# 2_Periph.net
KiCad netlist of a schematic drawn in Altium Designer
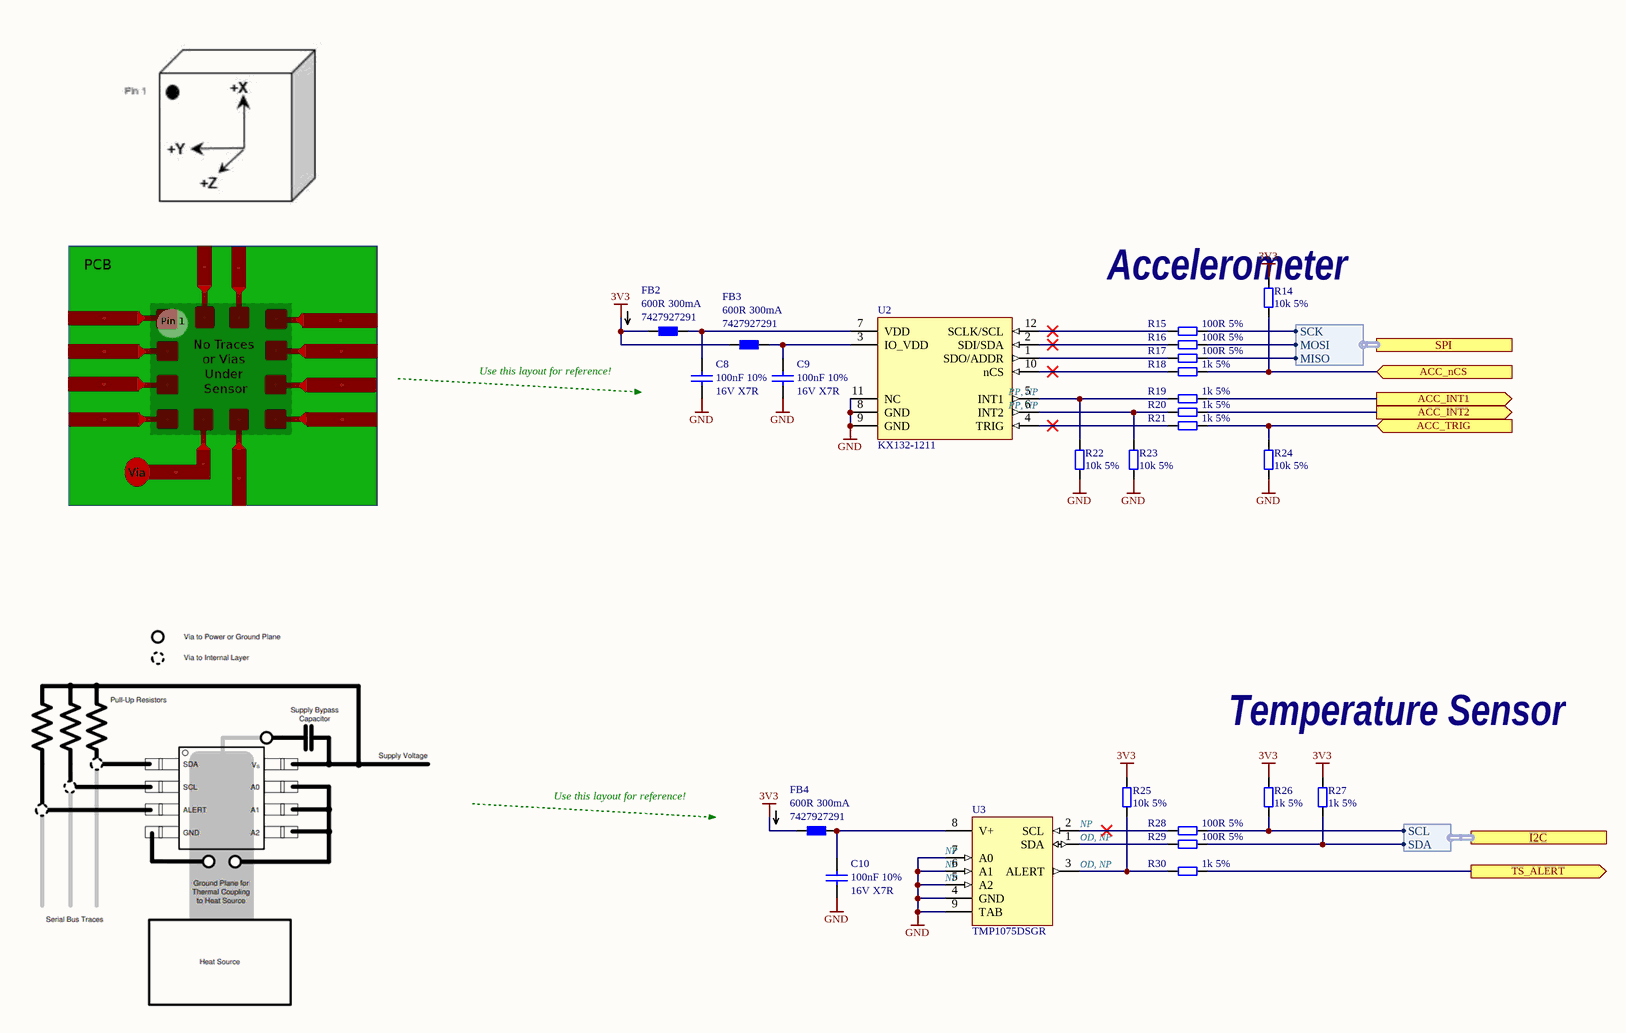
[diagram p0: 2_Periph.SchDoc]

(export (version "E")
  (design (tool "Eeschema 10.0.6"))
  (components
    (comp (ref "C8")
      (value "CC0402KRX7R7BB104")
      (footprint "CAP_0402_L")
      (description "CAP 0402 100nF 10% 16V X7R")
      (fields
        (field (name "PARAM 2") "16V X7R")
        (field (name "PARAM 1") "100nF 10%")
        (field (name "AUTHOR") "GH")
      )
      (libsource (lib "AuralixAltiumLib") (part "CAP_0402_100nF_10%_16V_X7R_CC0402KRX7R7BB104"))
    )
    (comp (ref "C9")
      (value "CC0402KRX7R7BB104")
      (footprint "CAP_0402_L")
      (description "CAP 0402 100nF 10% 16V X7R")
      (fields
        (field (name "PARAM 2") "16V X7R")
        (field (name "PARAM 1") "100nF 10%")
        (field (name "AUTHOR") "GH")
      )
      (libsource (lib "AuralixAltiumLib") (part "CAP_0402_100nF_10%_16V_X7R_CC0402KRX7R7BB104"))
    )
    (comp (ref "C10")
      (value "CC0402KRX7R7BB104")
      (footprint "CAP_0402_L")
      (description "CAP 0402 100nF 10% 16V X7R")
      (fields
        (field (name "PARAM 2") "16V X7R")
        (field (name "PARAM 1") "100nF 10%")
        (field (name "AUTHOR") "GH")
      )
      (libsource (lib "AuralixAltiumLib") (part "CAP_0402_100nF_10%_16V_X7R_CC0402KRX7R7BB104"))
    )
    (comp (ref "FB2")
      (value "7427927291")
      (footprint "BEAD_0402_L")
      (description "7427927291 - Ferrite Bead, 0402 [1005 Metric], 600 ohm, 300 mA, WE-CBF Series, 0.6 ohm, ± 25%")
      (fields
        (field (name "MFR NO 1") "7427927291")
        (field (name "PARAM 1") "600R 300mA")
        (field (name "AUTHOR") "TV")
      )
      (libsource (lib "AuralixAltiumLib") (part "BEAD_0402_600R_300mA_7427927291"))
    )
    (comp (ref "FB3")
      (value "7427927291")
      (footprint "BEAD_0402_L")
      (description "7427927291 - Ferrite Bead, 0402 [1005 Metric], 600 ohm, 300 mA, WE-CBF Series, 0.6 ohm, ± 25%")
      (fields
        (field (name "MFR NO 1") "7427927291")
        (field (name "PARAM 1") "600R 300mA")
        (field (name "AUTHOR") "TV")
      )
      (libsource (lib "AuralixAltiumLib") (part "BEAD_0402_600R_300mA_7427927291"))
    )
    (comp (ref "FB4")
      (value "7427927291")
      (footprint "BEAD_0402_L")
      (description "7427927291 - Ferrite Bead, 0402 [1005 Metric], 600 ohm, 300 mA, WE-CBF Series, 0.6 ohm, ± 25%")
      (fields
        (field (name "MFR NO 1") "7427927291")
        (field (name "PARAM 1") "600R 300mA")
        (field (name "AUTHOR") "TV")
      )
      (libsource (lib "AuralixAltiumLib") (part "BEAD_0402_600R_300mA_7427927291"))
    )
    (comp (ref "R14")
      (value "RC0402JR-0710KL")
      (footprint "RES_0402_L")
      (description "RES 0402 10k 5% 63mW 50V")
      (fields (field (name "PARAM 1") "10k 5%") (field (name "AUTHOR") "GH"))
      (libsource (lib "AuralixAltiumLib") (part "RES_0402_10k_5%_RC0402JR-0710KL"))
    )
    (comp (ref "R15")
      (value "RC0402JR-07100RL")
      (footprint "RES_0402_L")
      (description "RES 0402 100R 5% 63mW 50V")
      (fields (field (name "PARAM 1") "100R 5%") (field (name "AUTHOR") "GH"))
      (libsource (lib "AuralixAltiumLib") (part "RES_0402_100R_5% _RC0402JR-07100RL"))
    )
    (comp (ref "R16")
      (value "RC0402JR-07100RL")
      (footprint "RES_0402_L")
      (description "RES 0402 100R 5% 63mW 50V")
      (fields (field (name "PARAM 1") "100R 5%") (field (name "AUTHOR") "GH"))
      (libsource (lib "AuralixAltiumLib") (part "RES_0402_100R_5% _RC0402JR-07100RL"))
    )
    (comp (ref "R17")
      (value "RC0402JR-07100RL")
      (footprint "RES_0402_L")
      (description "RES 0402 100R 5% 63mW 50V")
      (fields (field (name "PARAM 1") "100R 5%") (field (name "AUTHOR") "GH"))
      (libsource (lib "AuralixAltiumLib") (part "RES_0402_100R_5% _RC0402JR-07100RL"))
    )
    (comp (ref "R18")
      (value "RC0402JR-071KL")
      (footprint "RES_0402_L")
      (description "RES 0402 1k 5% 63mW 50V")
      (fields (field (name "PARAM 1") "1k 5%") (field (name "AUTHOR") "GH"))
      (libsource (lib "AuralixAltiumLib") (part "RES_0402_1k_5%_RC0402JR-071KL"))
    )
    (comp (ref "R19")
      (value "RC0402JR-071KL")
      (footprint "RES_0402_L")
      (description "RES 0402 1k 5% 63mW 50V")
      (fields (field (name "PARAM 1") "1k 5%") (field (name "AUTHOR") "GH"))
      (libsource (lib "AuralixAltiumLib") (part "RES_0402_1k_5%_RC0402JR-071KL"))
    )
    (comp (ref "R20")
      (value "RC0402JR-071KL")
      (footprint "RES_0402_L")
      (description "RES 0402 1k 5% 63mW 50V")
      (fields (field (name "PARAM 1") "1k 5%") (field (name "AUTHOR") "GH"))
      (libsource (lib "AuralixAltiumLib") (part "RES_0402_1k_5%_RC0402JR-071KL"))
    )
    (comp (ref "R21")
      (value "RC0402JR-071KL")
      (footprint "RES_0402_L")
      (description "RES 0402 1k 5% 63mW 50V")
      (fields (field (name "PARAM 1") "1k 5%") (field (name "AUTHOR") "GH"))
      (libsource (lib "AuralixAltiumLib") (part "RES_0402_1k_5%_RC0402JR-071KL"))
    )
    (comp (ref "R22")
      (value "RC0402JR-0710KL")
      (footprint "RES_0402_L")
      (description "RES 0402 10k 5% 63mW 50V")
      (fields (field (name "PARAM 1") "10k 5%") (field (name "AUTHOR") "GH"))
      (libsource (lib "AuralixAltiumLib") (part "RES_0402_10k_5%_RC0402JR-0710KL"))
    )
    (comp (ref "R23")
      (value "RC0402JR-0710KL")
      (footprint "RES_0402_L")
      (description "RES 0402 10k 5% 63mW 50V")
      (fields (field (name "PARAM 1") "10k 5%") (field (name "AUTHOR") "GH"))
      (libsource (lib "AuralixAltiumLib") (part "RES_0402_10k_5%_RC0402JR-0710KL"))
    )
    (comp (ref "R24")
      (value "RC0402JR-0710KL")
      (footprint "RES_0402_L")
      (description "RES 0402 10k 5% 63mW 50V")
      (fields (field (name "PARAM 1") "10k 5%") (field (name "AUTHOR") "GH"))
      (libsource (lib "AuralixAltiumLib") (part "RES_0402_10k_5%_RC0402JR-0710KL"))
    )
    (comp (ref "R25")
      (value "RC0402JR-0710KL")
      (footprint "RES_0402_L")
      (description "RES 0402 10k 5% 63mW 50V")
      (fields (field (name "PARAM 1") "10k 5%") (field (name "AUTHOR") "GH"))
      (libsource (lib "AuralixAltiumLib") (part "RES_0402_10k_5%_RC0402JR-0710KL"))
    )
    (comp (ref "R26")
      (value "RC0402JR-071KL")
      (footprint "RES_0402_L")
      (description "RES 0402 1k 5% 63mW 50V")
      (fields (field (name "PARAM 1") "1k 5%") (field (name "AUTHOR") "GH"))
      (libsource (lib "") (part "RES_0402_1k_5%_RC0402JR-071KL_1"))
    )
    (comp (ref "R27")
      (value "RC0402JR-071KL")
      (footprint "RES_0402_L")
      (description "RES 0402 1k 5% 63mW 50V")
      (fields (field (name "PARAM 1") "1k 5%") (field (name "AUTHOR") "GH"))
      (libsource (lib "") (part "RES_0402_1k_5%_RC0402JR-071KL_1"))
    )
    (comp (ref "R28")
      (value "RC0402JR-07100RL")
      (footprint "RES_0402_L")
      (description "RES 0402 100R 5% 63mW 50V")
      (fields (field (name "PARAM 1") "100R 5%") (field (name "AUTHOR") "GH"))
      (libsource (lib "AuralixAltiumLib") (part "RES_0402_100R_5% _RC0402JR-07100RL"))
    )
    (comp (ref "R29")
      (value "RC0402JR-07100RL")
      (footprint "RES_0402_L")
      (description "RES 0402 100R 5% 63mW 50V")
      (fields (field (name "PARAM 1") "100R 5%") (field (name "AUTHOR") "GH"))
      (libsource (lib "AuralixAltiumLib") (part "RES_0402_100R_5% _RC0402JR-07100RL"))
    )
    (comp (ref "R30")
      (value "RC0402JR-071KL")
      (footprint "RES_0402_L")
      (description "RES 0402 1k 5% 63mW 50V")
      (fields (field (name "PARAM 1") "1k 5%") (field (name "AUTHOR") "GH"))
      (libsource (lib "AuralixAltiumLib") (part "RES_0402_1k_5%_RC0402JR-071KL"))
    )
    (comp (ref "U2")
      (value "KX132-1211")
      (footprint "PQFN12P50_200X200")
      (fields (field (name "MFR NO 1") "KX132-1211") (field (name "AUTHOR") "GH"))
      (libsource (lib "AuralixAltiumLib") (part "IC_KX132-1211"))
    )
    (comp (ref "U3")
      (value "TMP1075DSGR")
      (footprint "SON9P50_200X200T160X90")
      (description "TMP1075DSGR -  Board Mount Temperature Sensor Digital, Local -55°C ~ 125°C 12 b 8-WSON (2x2)")
      (fields (field (name "MFR NO 1") "TMP1075DSGR") (field (name "AUTHOR") "GH"))
      (libsource (lib "AuralixAltiumLib") (part "IC_TMP1075DSGR"))
    )
  )
  (nets
    (net (code "3") (name "/ACC_INT1") (class "Default")
      (node (ref "R19") (pin "2") (pinfunction "2_2") (pintype "passive"))
    )
    (net (code "4") (name "/ACC_INT2") (class "Default")
      (node (ref "R20") (pin "2") (pinfunction "2_2") (pintype "passive"))
    )
    (net (code "5") (name "/ACC_TRIG") (class "Default")
      (node (ref "R21") (pin "2") (pinfunction "2_2") (pintype "passive"))
      (node (ref "R24") (pin "1") (pinfunction "1_1") (pintype "passive"))
    )
    (net (code "6") (name "/ACC_nCS") (class "Default")
      (node (ref "R14") (pin "2") (pinfunction "2_2") (pintype "passive"))
      (node (ref "R18") (pin "2") (pinfunction "2_2") (pintype "passive"))
    )
    (net (code "7") (name "/MISO") (class "Default")
      (node (ref "R17") (pin "2") (pinfunction "2_2") (pintype "passive"))
    )
    (net (code "8") (name "/MOSI") (class "Default")
      (node (ref "R16") (pin "2") (pinfunction "2_2") (pintype "passive"))
    )
    (net (code "9") (name "/SCK") (class "Default")
      (node (ref "R15") (pin "2") (pinfunction "2_2") (pintype "passive"))
    )
    (net (code "10") (name "/SCL") (class "Default")
      (node (ref "R26") (pin "2") (pinfunction "2_2") (pintype "passive"))
      (node (ref "R28") (pin "2") (pinfunction "2_2") (pintype "passive"))
    )
    (net (code "11") (name "/SDA") (class "Default")
      (node (ref "R27") (pin "2") (pinfunction "2_2") (pintype "passive"))
      (node (ref "R29") (pin "2") (pinfunction "2_2") (pintype "passive"))
    )
    (net (code "12") (name "/TS_ALERT") (class "Default")
      (node (ref "R30") (pin "2") (pinfunction "2_2") (pintype "passive"))
    )
    (net (code "15") (name "3V3") (class "Default")
      (node (ref "FB2") (pin "2") (pinfunction "2_2") (pintype "passive"))
      (node (ref "FB3") (pin "2") (pinfunction "2_2") (pintype "passive"))
      (node (ref "FB4") (pin "2") (pinfunction "2_2") (pintype "passive"))
      (node (ref "R14") (pin "1") (pinfunction "1_1") (pintype "passive"))
      (node (ref "R25") (pin "1") (pinfunction "1_1") (pintype "passive"))
      (node (ref "R26") (pin "1") (pinfunction "1_1") (pintype "passive"))
      (node (ref "R27") (pin "1") (pinfunction "1_1") (pintype "passive"))
    )
    (net (code "16") (name "GND") (class "Default")
      (node (ref "C10") (pin "2") (pinfunction "2_2") (pintype "passive"))
      (node (ref "C8") (pin "2") (pinfunction "2_2") (pintype "passive"))
      (node (ref "C9") (pin "2") (pinfunction "2_2") (pintype "passive"))
      (node (ref "R22") (pin "2") (pinfunction "2_2") (pintype "passive"))
      (node (ref "R23") (pin "2") (pinfunction "2_2") (pintype "passive"))
      (node (ref "R24") (pin "2") (pinfunction "2_2") (pintype "passive"))
      (node (ref "U2") (pin "11") (pinfunction "NC_11") (pintype "passive"))
      (node (ref "U2") (pin "8") (pinfunction "GND_8") (pintype "power_in"))
      (node (ref "U2") (pin "9") (pinfunction "GND_9") (pintype "power_in"))
      (node (ref "U3") (pin "4") (pinfunction "GND_4") (pintype "power_in"))
      (node (ref "U3") (pin "5") (pinfunction "A2_5") (pintype "input"))
      (node (ref "U3") (pin "6") (pinfunction "A1_6") (pintype "input"))
      (node (ref "U3") (pin "7") (pinfunction "A0_7") (pintype "input"))
      (node (ref "U3") (pin "9") (pinfunction "TAB_9") (pintype "power_in"))
    )
    (net (code "17") (name "Net-(U2-INT1)") (class "Default")
      (node (ref "R19") (pin "1") (pinfunction "1_1") (pintype "passive"))
      (node (ref "R22") (pin "1") (pinfunction "1_1") (pintype "passive"))
      (node (ref "U2") (pin "5") (pinfunction "INT1_5") (pintype "output"))
    )
    (net (code "18") (name "Net-(U2-INT2)") (class "Default")
      (node (ref "R20") (pin "1") (pinfunction "1_1") (pintype "passive"))
      (node (ref "R23") (pin "1") (pinfunction "1_1") (pintype "passive"))
      (node (ref "U2") (pin "6") (pinfunction "INT2_6") (pintype "output"))
    )
    (net (code "19") (name "Net-(U2-IO_VDD)") (class "Default")
      (node (ref "C9") (pin "1") (pinfunction "1_1") (pintype "passive"))
      (node (ref "FB3") (pin "1") (pinfunction "1_1") (pintype "passive"))
      (node (ref "U2") (pin "3") (pinfunction "IO_VDD_3") (pintype "power_in"))
    )
    (net (code "20") (name "Net-(U2-SCLK{slash}SCL)") (class "Default")
      (node (ref "R15") (pin "1") (pinfunction "1_1") (pintype "passive"))
      (node (ref "U2") (pin "12") (pinfunction "SCLK/SCL_12") (pintype "input"))
    )
    (net (code "21") (name "Net-(U2-SDI{slash}SDA)") (class "Default")
      (node (ref "R16") (pin "1") (pinfunction "1_1") (pintype "passive"))
      (node (ref "U2") (pin "2") (pinfunction "SDI/SDA_2") (pintype "input"))
    )
    (net (code "22") (name "Net-(U2-SDO{slash}ADDR)") (class "Default")
      (node (ref "R17") (pin "1") (pinfunction "1_1") (pintype "passive"))
      (node (ref "U2") (pin "1") (pinfunction "SDO/ADDR_1") (pintype "output"))
    )
    (net (code "23") (name "Net-(U2-TRIG)") (class "Default")
      (node (ref "R21") (pin "1") (pinfunction "1_1") (pintype "passive"))
      (node (ref "U2") (pin "4") (pinfunction "TRIG_4") (pintype "input"))
    )
    (net (code "24") (name "Net-(U2-VDD)") (class "Default")
      (node (ref "C8") (pin "1") (pinfunction "1_1") (pintype "passive"))
      (node (ref "FB2") (pin "1") (pinfunction "1_1") (pintype "passive"))
      (node (ref "U2") (pin "7") (pinfunction "VDD_7") (pintype "power_in"))
    )
    (net (code "25") (name "Net-(U2-nCS)") (class "Default")
      (node (ref "R18") (pin "1") (pinfunction "1_1") (pintype "passive"))
      (node (ref "U2") (pin "10") (pinfunction "nCS_10") (pintype "input"))
    )
    (net (code "26") (name "Net-(U3-ALERT)") (class "Default")
      (node (ref "R25") (pin "2") (pinfunction "2_2") (pintype "passive"))
      (node (ref "R30") (pin "1") (pinfunction "1_1") (pintype "passive"))
      (node (ref "U3") (pin "3") (pinfunction "ALERT_3") (pintype "output"))
    )
    (net (code "27") (name "Net-(U3-SCL)") (class "Default")
      (node (ref "R28") (pin "1") (pinfunction "1_1") (pintype "passive"))
      (node (ref "U3") (pin "2") (pinfunction "SCL_2") (pintype "input"))
    )
    (net (code "28") (name "Net-(U3-SDA)") (class "Default")
      (node (ref "R29") (pin "1") (pinfunction "1_1") (pintype "passive"))
      (node (ref "U3") (pin "1") (pinfunction "SDA_1") (pintype "bidirectional"))
    )
    (net (code "29") (name "Net-(U3-V+)") (class "Default")
      (node (ref "C10") (pin "1") (pinfunction "1_1") (pintype "passive"))
      (node (ref "FB4") (pin "1") (pinfunction "1_1") (pintype "passive"))
      (node (ref "U3") (pin "8") (pinfunction "V+_8") (pintype "power_in"))
    )
  )
)
